# murdock_mcu_v1.net
KiCad netlist of a schematic drawn in EAGLE
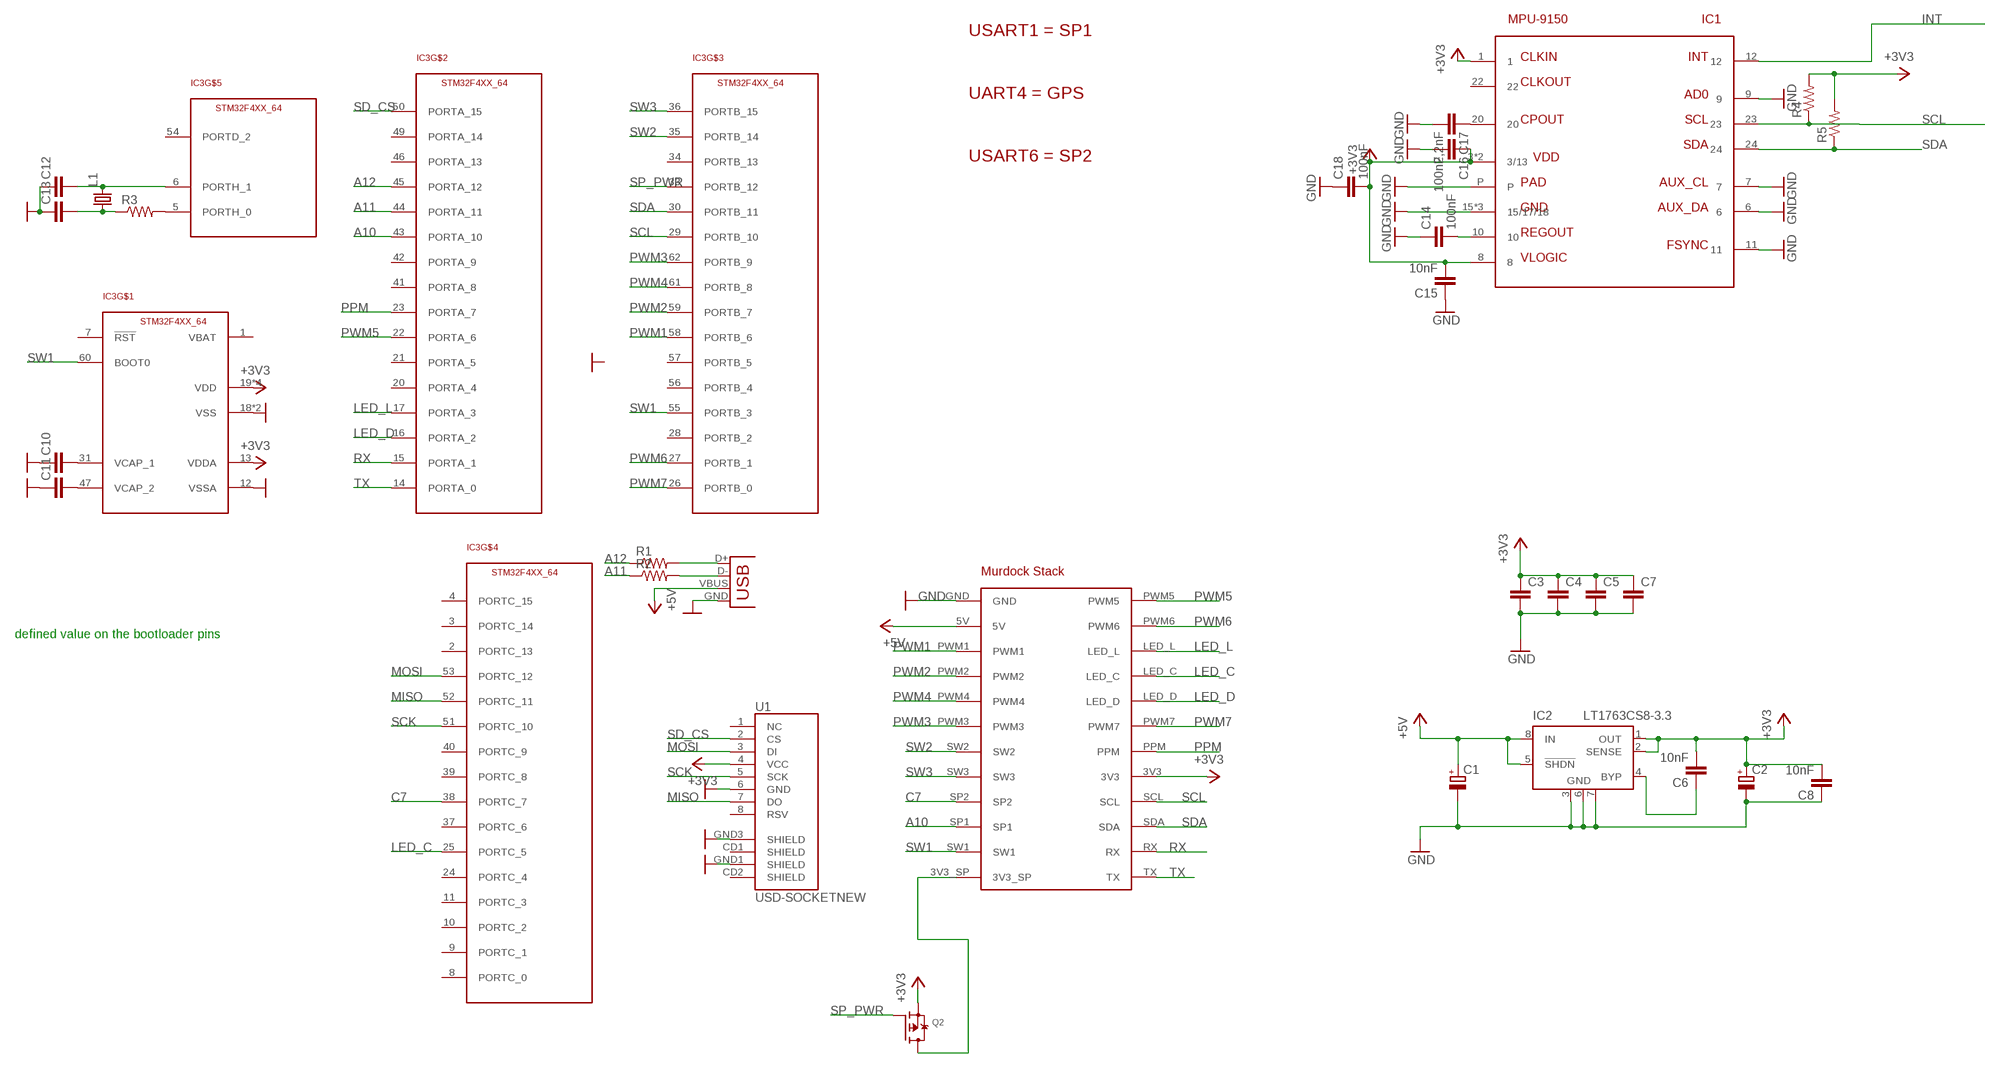
[diagram p0: schematic, sheet 1]

(export (version "E")
  (design (tool "Eeschema 10.0.6"))
  (components
    (comp (ref "C1")
      (value "CPOL-EUSMCD")
      (footprint "eagle-import:SMC_D")
      (libsource (lib "eagle-import") (part "CPOL-EUSMCD"))
    )
    (comp (ref "C2")
      (value "CPOL-EUSMCD")
      (footprint "eagle-import:SMC_D")
      (libsource (lib "eagle-import") (part "CPOL-EUSMCD"))
    )
    (comp (ref "C3")
      (value "CAP0402-CAP")
      (footprint "eagle-import:0402-CAP")
      (libsource (lib "eagle-import") (part "SparkFun-Capacitors_CAP0402-CAP"))
    )
    (comp (ref "C4")
      (value "CAP0402-CAP")
      (footprint "eagle-import:0402-CAP")
      (libsource (lib "eagle-import") (part "SparkFun-Capacitors_CAP0402-CAP"))
    )
    (comp (ref "C5")
      (value "CAP0402-CAP")
      (footprint "eagle-import:0402-CAP")
      (libsource (lib "eagle-import") (part "SparkFun-Capacitors_CAP0402-CAP"))
    )
    (comp (ref "C6")
      (value "10nF")
      (footprint "eagle-import:C0402")
      (libsource (lib "eagle-import") (part "C-EUC0402"))
    )
    (comp (ref "C7")
      (value "CAP0402-CAP")
      (footprint "eagle-import:0402-CAP")
      (libsource (lib "eagle-import") (part "SparkFun-Capacitors_CAP0402-CAP"))
    )
    (comp (ref "C8")
      (value "10nF")
      (footprint "eagle-import:C0402")
      (libsource (lib "eagle-import") (part "C-EUC0402"))
    )
    (comp (ref "C10")
      (value "CAP0805")
      (footprint "eagle-import:0805")
      (libsource (lib "eagle-import") (part "SparkFun-Capacitors_CAP0805"))
    )
    (comp (ref "C11")
      (value "CAP0805")
      (footprint "eagle-import:0805")
      (libsource (lib "eagle-import") (part "SparkFun-Capacitors_CAP0805"))
    )
    (comp (ref "C12")
      (value "CAP0402-CAP")
      (footprint "eagle-import:0402-CAP")
      (libsource (lib "eagle-import") (part "SparkFun-Capacitors_CAP0402-CAP"))
    )
    (comp (ref "C13")
      (value "CAP0402-CAP")
      (footprint "eagle-import:0402-CAP")
      (libsource (lib "eagle-import") (part "SparkFun-Capacitors_CAP0402-CAP"))
    )
    (comp (ref "C14")
      (value "100nF")
      (footprint "eagle-import:0402-CAP")
      (libsource (lib "eagle-import") (part "CAP0402-CAP"))
    )
    (comp (ref "C15")
      (value "10nF")
      (footprint "eagle-import:0402-CAP")
      (libsource (lib "eagle-import") (part "CAP0402-CAP"))
    )
    (comp (ref "C16")
      (value "100nF")
      (footprint "eagle-import:0402-CAP")
      (libsource (lib "eagle-import") (part "CAP0402-CAP"))
    )
    (comp (ref "C17")
      (value "2,2nF")
      (footprint "eagle-import:0402-CAP")
      (libsource (lib "eagle-import") (part "CAP0402-CAP"))
    )
    (comp (ref "C18")
      (value "100nF")
      (footprint "eagle-import:0402-CAP")
      (libsource (lib "eagle-import") (part "CAP0402-CAP"))
    )
    (comp (ref "IC1")
      (value "MPU-9150")
      (footprint "eagle-import:QFN24")
      (libsource (lib "eagle-import") (part "MPU-9150"))
    )
    (comp (ref "IC2")
      (value "LT1763CS8-3.3")
      (footprint "eagle-import:SOIC8")
      (libsource (lib "eagle-import") (part "LT1763CS8-3.3"))
    )
    (comp (ref "IC3")
      (value "STM32F4XX_64")
      (footprint "eagle-import:TQFP64")
      (libsource (lib "eagle-import") (part "STM32F4XX_64"))
    )
    (comp (ref "L1")
      (value "X22-OSCILLATOR")
      (footprint "eagle-import:X22")
      (libsource (lib "eagle-import") (part "X22-OSCILLATOR"))
    )
    (comp (ref "Q2")
      (value "MOSFET-P")
      (footprint "eagle-import:SOT23-R")
      (libsource (lib "eagle-import") (part "MOSFET-P"))
    )
    (comp (ref "R1")
      (value "RESISTOR0402-RES")
      (footprint "eagle-import:0402-RES")
      (libsource (lib "eagle-import") (part "SparkFun-Resistors_RESISTOR0402-RES"))
    )
    (comp (ref "R2")
      (value "RESISTOR0402-RES")
      (footprint "eagle-import:0402-RES")
      (libsource (lib "eagle-import") (part "SparkFun-Resistors_RESISTOR0402-RES"))
    )
    (comp (ref "R3")
      (value "RESISTOR0402-RES")
      (footprint "eagle-import:0402-RES")
      (libsource (lib "eagle-import") (part "SparkFun-Resistors_RESISTOR0402-RES"))
    )
    (comp (ref "R4")
      (value "RESISTOR0402-RES")
      (footprint "eagle-import:0402-RES")
      (libsource (lib "eagle-import") (part "RESISTOR0402-RES"))
    )
    (comp (ref "R5")
      (value "RESISTOR0402-RES")
      (footprint "eagle-import:0402-RES")
      (libsource (lib "eagle-import") (part "RESISTOR0402-RES"))
    )
    (comp (ref "U1")
      (value "USD-SOCKETNEW")
      (footprint "eagle-import:MICRO-SD-SOCKET-PP")
      (libsource (lib "eagle-import") (part "USD-SOCKETNEW"))
    )
    (comp (ref "X1")
      (value "USBSMD")
      (footprint "eagle-import:USB-MINIB")
      (libsource (lib "eagle-import") (part "USBSMD"))
    )
    (comp (ref "X2")
      (value "MURDOCK_STACK")
      (footprint "eagle-import:MURDOCK_STACK")
      (libsource (lib "eagle-import") (part "MURDOCK_STACK"))
    )
  )
  (nets
    (net (code "1") (name "+3V3") (class "Default")
      (node (ref "C15") (pin "2") (pinfunction "2_2") (pintype "passive"))
      (node (ref "C16") (pin "1") (pinfunction "1_1") (pintype "passive"))
      (node (ref "C18") (pin "2") (pinfunction "2_2") (pintype "passive"))
      (node (ref "C2") (pin "+") (pinfunction "+_+") (pintype "passive"))
      (node (ref "C3") (pin "1") (pinfunction "1_1") (pintype "passive"))
      (node (ref "C4") (pin "1") (pinfunction "1_1") (pintype "passive"))
      (node (ref "C5") (pin "1") (pinfunction "1_1") (pintype "passive"))
      (node (ref "C6") (pin "2") (pinfunction "2_2") (pintype "passive"))
      (node (ref "C7") (pin "1") (pinfunction "1_1") (pintype "passive"))
      (node (ref "C8") (pin "2") (pinfunction "2_2") (pintype "passive"))
      (node (ref "IC1") (pin "1") (pinfunction "1_1") (pintype "bidirectional"))
      (node (ref "IC1") (pin "13") (pinfunction "3/13_13") (pintype "bidirectional"))
      (node (ref "IC1") (pin "3") (pinfunction "3/13_3") (pintype "bidirectional"))
      (node (ref "IC1") (pin "8") (pinfunction "8_8") (pintype "bidirectional"))
      (node (ref "IC2") (pin "1") (pinfunction "OUT_1") (pintype "passive"))
      (node (ref "IC2") (pin "2") (pinfunction "SENSE_2") (pintype "input"))
      (node (ref "IC3") (pin "13") (pinfunction "VDDA_13") (pintype "bidirectional"))
      (node (ref "IC3") (pin "19") (pinfunction "VDD_19") (pintype "bidirectional"))
      (node (ref "IC3") (pin "32") (pinfunction "VDD_32") (pintype "bidirectional"))
      (node (ref "IC3") (pin "48") (pinfunction "VDD_48") (pintype "bidirectional"))
      (node (ref "IC3") (pin "64") (pinfunction "VDD_64") (pintype "bidirectional"))
      (node (ref "Q2") (pin "2") (pinfunction "S_2") (pintype "passive"))
      (node (ref "R4") (pin "2") (pinfunction "2_2") (pintype "passive"))
      (node (ref "R5") (pin "2") (pinfunction "2_2") (pintype "passive"))
      (node (ref "U1") (pin "4") (pinfunction "VCC_4") (pintype "bidirectional"))
      (node (ref "X2") (pin "3V3") (pinfunction "3V3_3V3") (pintype "bidirectional"))
    )
    (net (code "2") (name "+5V") (class "Default")
      (node (ref "C1") (pin "+") (pinfunction "+_+") (pintype "passive"))
      (node (ref "IC2") (pin "5") (pinfunction "~{SHDN}_5") (pintype "input"))
      (node (ref "IC2") (pin "8") (pinfunction "IN_8") (pintype "input"))
      (node (ref "X1") (pin "VBUS") (pinfunction "VBUS_VBUS") (pintype "bidirectional"))
      (node (ref "X2") (pin "5V") (pinfunction "5V_5V") (pintype "bidirectional"))
    )
    (net (code "3") (name "A10") (class "Default")
      (node (ref "IC3") (pin "43") (pinfunction "PORTA_10_43") (pintype "bidirectional"))
      (node (ref "X2") (pin "SP1") (pinfunction "SP1_SP1") (pintype "bidirectional"))
    )
    (net (code "4") (name "A11") (class "Default")
      (node (ref "IC3") (pin "44") (pinfunction "PORTA_11_44") (pintype "bidirectional"))
      (node (ref "R2") (pin "1") (pinfunction "1_1") (pintype "passive"))
    )
    (net (code "5") (name "A12") (class "Default")
      (node (ref "IC3") (pin "45") (pinfunction "PORTA_12_45") (pintype "bidirectional"))
      (node (ref "R1") (pin "1") (pinfunction "1_1") (pintype "passive"))
    )
    (net (code "6") (name "C7") (class "Default")
      (node (ref "IC3") (pin "38") (pinfunction "PORTC_7_38") (pintype "bidirectional"))
      (node (ref "X2") (pin "SP2") (pinfunction "SP2_SP2") (pintype "bidirectional"))
    )
    (net (code "7") (name "GND") (class "Default")
      (node (ref "C1") (pin "-") (pinfunction "-_-") (pintype "passive"))
      (node (ref "C10") (pin "1") (pinfunction "1_1") (pintype "passive"))
      (node (ref "C11") (pin "1") (pinfunction "1_1") (pintype "passive"))
      (node (ref "C12") (pin "1") (pinfunction "1_1") (pintype "passive"))
      (node (ref "C13") (pin "1") (pinfunction "1_1") (pintype "passive"))
      (node (ref "C14") (pin "1") (pinfunction "1_1") (pintype "passive"))
      (node (ref "C15") (pin "1") (pinfunction "1_1") (pintype "passive"))
      (node (ref "C16") (pin "2") (pinfunction "2_2") (pintype "passive"))
      (node (ref "C17") (pin "2") (pinfunction "2_2") (pintype "passive"))
      (node (ref "C18") (pin "1") (pinfunction "1_1") (pintype "passive"))
      (node (ref "C2") (pin "-") (pinfunction "-_-") (pintype "passive"))
      (node (ref "C3") (pin "2") (pinfunction "2_2") (pintype "passive"))
      (node (ref "C4") (pin "2") (pinfunction "2_2") (pintype "passive"))
      (node (ref "C5") (pin "2") (pinfunction "2_2") (pintype "passive"))
      (node (ref "C7") (pin "2") (pinfunction "2_2") (pintype "passive"))
      (node (ref "C8") (pin "1") (pinfunction "1_1") (pintype "passive"))
      (node (ref "IC1") (pin "11") (pinfunction "11_11") (pintype "bidirectional"))
      (node (ref "IC1") (pin "15") (pinfunction "15/17/18_15") (pintype "bidirectional"))
      (node (ref "IC1") (pin "17") (pinfunction "15/17/18_17") (pintype "bidirectional"))
      (node (ref "IC1") (pin "18") (pinfunction "15/17/18_18") (pintype "bidirectional"))
      (node (ref "IC1") (pin "6") (pinfunction "6_6") (pintype "bidirectional"))
      (node (ref "IC1") (pin "7") (pinfunction "7_7") (pintype "bidirectional"))
      (node (ref "IC1") (pin "9") (pinfunction "9_9") (pintype "bidirectional"))
      (node (ref "IC1") (pin "P") (pinfunction "P_P") (pintype "bidirectional"))
      (node (ref "IC2") (pin "3") (pinfunction "GND_3") (pintype "power_in"))
      (node (ref "IC2") (pin "6") (pinfunction "GND_6") (pintype "power_in"))
      (node (ref "IC2") (pin "7") (pinfunction "GND_7") (pintype "power_in"))
      (node (ref "IC3") (pin "12") (pinfunction "VSSA_12") (pintype "bidirectional"))
      (node (ref "IC3") (pin "18") (pinfunction "VSS_18") (pintype "bidirectional"))
      (node (ref "IC3") (pin "63") (pinfunction "VSS_63") (pintype "bidirectional"))
      (node (ref "U1") (pin "6") (pinfunction "GND_6") (pintype "bidirectional"))
      (node (ref "U1") (pin "GND1") (pinfunction "SHIELD_GND1") (pintype "bidirectional"))
      (node (ref "U1") (pin "GND3") (pinfunction "SHIELD_GND3") (pintype "bidirectional"))
      (node (ref "X1") (pin "GND") (pinfunction "GND_GND") (pintype "bidirectional"))
      (node (ref "X2") (pin "GND") (pinfunction "GND_GND") (pintype "bidirectional"))
    )
    (net (code "8") (name "INT") (class "Default")
      (node (ref "IC1") (pin "12") (pinfunction "12_12") (pintype "bidirectional"))
    )
    (net (code "9") (name "LED_C") (class "Default")
      (node (ref "IC3") (pin "25") (pinfunction "PORTC_5_25") (pintype "bidirectional"))
      (node (ref "X2") (pin "LED_C") (pinfunction "LED_C_LED_C") (pintype "bidirectional"))
    )
    (net (code "10") (name "LED_D") (class "Default")
      (node (ref "IC3") (pin "16") (pinfunction "PORTA_2_16") (pintype "bidirectional"))
      (node (ref "X2") (pin "LED_D") (pinfunction "LED_D_LED_D") (pintype "bidirectional"))
    )
    (net (code "11") (name "LED_L") (class "Default")
      (node (ref "IC3") (pin "17") (pinfunction "PORTA_3_17") (pintype "bidirectional"))
      (node (ref "X2") (pin "LED_L") (pinfunction "LED_L_LED_L") (pintype "bidirectional"))
    )
    (net (code "12") (name "MISO") (class "Default")
      (node (ref "IC3") (pin "52") (pinfunction "PORTC_11_52") (pintype "bidirectional"))
      (node (ref "U1") (pin "7") (pinfunction "DO_7") (pintype "bidirectional"))
    )
    (net (code "13") (name "MOSI") (class "Default")
      (node (ref "IC3") (pin "53") (pinfunction "PORTC_12_53") (pintype "bidirectional"))
      (node (ref "U1") (pin "3") (pinfunction "DI_3") (pintype "bidirectional"))
    )
    (net (code "14") (name "Net-(C13-Pad2)") (class "Default")
      (node (ref "C13") (pin "2") (pinfunction "2_2") (pintype "passive"))
      (node (ref "L1") (pin "1") (pinfunction "1_1") (pintype "passive"))
      (node (ref "R3") (pin "1") (pinfunction "1_1") (pintype "passive"))
    )
    (net (code "15") (name "Net-(C14-Pad2)") (class "Default")
      (node (ref "C14") (pin "2") (pinfunction "2_2") (pintype "passive"))
      (node (ref "IC1") (pin "10") (pinfunction "10_10") (pintype "bidirectional"))
    )
    (net (code "16") (name "Net-(C17-Pad1)") (class "Default")
      (node (ref "C17") (pin "1") (pinfunction "1_1") (pintype "passive"))
      (node (ref "IC1") (pin "20") (pinfunction "20_20") (pintype "bidirectional"))
    )
    (net (code "17") (name "Net-(IC2-BYP)") (class "Default")
      (node (ref "C6") (pin "1") (pinfunction "1_1") (pintype "passive"))
      (node (ref "IC2") (pin "4") (pinfunction "BYP_4") (pintype "input"))
    )
    (net (code "18") (name "Net-(IC3A-VCAP_1)") (class "Default")
      (node (ref "C10") (pin "2") (pinfunction "2_2") (pintype "passive"))
      (node (ref "IC3") (pin "31") (pinfunction "VCAP_1_31") (pintype "bidirectional"))
    )
    (net (code "19") (name "Net-(IC3A-VCAP_2)") (class "Default")
      (node (ref "C11") (pin "2") (pinfunction "2_2") (pintype "passive"))
      (node (ref "IC3") (pin "47") (pinfunction "VCAP_2_47") (pintype "bidirectional"))
    )
    (net (code "20") (name "Net-(IC3E-PORTH_0)") (class "Default")
      (node (ref "IC3") (pin "5") (pinfunction "PORTH_0_5") (pintype "bidirectional"))
      (node (ref "R3") (pin "2") (pinfunction "2_2") (pintype "passive"))
    )
    (net (code "21") (name "Net-(IC3E-PORTH_1)") (class "Default")
      (node (ref "C12") (pin "2") (pinfunction "2_2") (pintype "passive"))
      (node (ref "IC3") (pin "6") (pinfunction "PORTH_1_6") (pintype "bidirectional"))
      (node (ref "L1") (pin "3") (pinfunction "2_3") (pintype "passive"))
    )
    (net (code "22") (name "Net-(Q2-D)") (class "Default")
      (node (ref "Q2") (pin "3") (pinfunction "D_3") (pintype "passive"))
      (node (ref "X2") (pin "3V3_SP") (pinfunction "3V3_SP_3V3_SP") (pintype "bidirectional"))
    )
    (net (code "23") (name "Net-(R1-Pad2)") (class "Default")
      (node (ref "R1") (pin "2") (pinfunction "2_2") (pintype "passive"))
      (node (ref "X1") (pin "D+") (pinfunction "D+_D+") (pintype "bidirectional"))
    )
    (net (code "24") (name "Net-(R2-Pad2)") (class "Default")
      (node (ref "R2") (pin "2") (pinfunction "2_2") (pintype "passive"))
      (node (ref "X1") (pin "D-") (pinfunction "D-_D-") (pintype "bidirectional"))
    )
    (net (code "25") (name "PPM") (class "Default")
      (node (ref "IC3") (pin "23") (pinfunction "PORTA_7_23") (pintype "bidirectional"))
      (node (ref "X2") (pin "PPM") (pinfunction "PPM_PPM") (pintype "bidirectional"))
    )
    (net (code "26") (name "PWM1") (class "Default")
      (node (ref "IC3") (pin "58") (pinfunction "PORTB_6_58") (pintype "bidirectional"))
      (node (ref "X2") (pin "PWM1") (pinfunction "PWM1_PWM1") (pintype "bidirectional"))
    )
    (net (code "27") (name "PWM2") (class "Default")
      (node (ref "IC3") (pin "59") (pinfunction "PORTB_7_59") (pintype "bidirectional"))
      (node (ref "X2") (pin "PWM2") (pinfunction "PWM2_PWM2") (pintype "bidirectional"))
    )
    (net (code "28") (name "PWM3") (class "Default")
      (node (ref "IC3") (pin "62") (pinfunction "PORTB_9_62") (pintype "bidirectional"))
      (node (ref "X2") (pin "PWM3") (pinfunction "PWM3_PWM3") (pintype "bidirectional"))
    )
    (net (code "29") (name "PWM4") (class "Default")
      (node (ref "IC3") (pin "61") (pinfunction "PORTB_8_61") (pintype "bidirectional"))
      (node (ref "X2") (pin "PWM4") (pinfunction "PWM4_PWM4") (pintype "bidirectional"))
    )
    (net (code "30") (name "PWM5") (class "Default")
      (node (ref "IC3") (pin "22") (pinfunction "PORTA_6_22") (pintype "bidirectional"))
      (node (ref "X2") (pin "PWM5") (pinfunction "PWM5_PWM5") (pintype "bidirectional"))
    )
    (net (code "31") (name "PWM6") (class "Default")
      (node (ref "IC3") (pin "27") (pinfunction "PORTB_1_27") (pintype "bidirectional"))
      (node (ref "X2") (pin "PWM6") (pinfunction "PWM6_PWM6") (pintype "bidirectional"))
    )
    (net (code "32") (name "PWM7") (class "Default")
      (node (ref "IC3") (pin "26") (pinfunction "PORTB_0_26") (pintype "bidirectional"))
      (node (ref "X2") (pin "PWM7") (pinfunction "PWM7_PWM7") (pintype "bidirectional"))
    )
    (net (code "33") (name "RX") (class "Default")
      (node (ref "IC3") (pin "15") (pinfunction "PORTA_1_15") (pintype "bidirectional"))
      (node (ref "X2") (pin "RX") (pinfunction "RX_RX") (pintype "bidirectional"))
    )
    (net (code "34") (name "SCK") (class "Default")
      (node (ref "IC3") (pin "51") (pinfunction "PORTC_10_51") (pintype "bidirectional"))
      (node (ref "U1") (pin "5") (pinfunction "SCK_5") (pintype "bidirectional"))
    )
    (net (code "35") (name "SCL") (class "Default")
      (node (ref "IC1") (pin "23") (pinfunction "23_23") (pintype "bidirectional"))
      (node (ref "IC3") (pin "29") (pinfunction "PORTB_10_29") (pintype "bidirectional"))
      (node (ref "R4") (pin "1") (pinfunction "1_1") (pintype "passive"))
      (node (ref "X2") (pin "SCL") (pinfunction "SCL_SCL") (pintype "bidirectional"))
    )
    (net (code "36") (name "SDA") (class "Default")
      (node (ref "IC1") (pin "24") (pinfunction "24_24") (pintype "bidirectional"))
      (node (ref "IC3") (pin "30") (pinfunction "PORTB_11_30") (pintype "bidirectional"))
      (node (ref "R5") (pin "1") (pinfunction "1_1") (pintype "passive"))
      (node (ref "X2") (pin "SDA") (pinfunction "SDA_SDA") (pintype "bidirectional"))
    )
    (net (code "37") (name "SD_CS") (class "Default")
      (node (ref "IC3") (pin "50") (pinfunction "PORTA_15_50") (pintype "bidirectional"))
      (node (ref "U1") (pin "2") (pinfunction "CS_2") (pintype "bidirectional"))
    )
    (net (code "38") (name "SP_PWR") (class "Default")
      (node (ref "IC3") (pin "33") (pinfunction "PORTB_12_33") (pintype "bidirectional"))
      (node (ref "Q2") (pin "1") (pinfunction "G_1") (pintype "passive"))
    )
    (net (code "39") (name "SW1") (class "Default")
      (node (ref "IC3") (pin "55") (pinfunction "PORTB_3_55") (pintype "bidirectional"))
      (node (ref "IC3") (pin "60") (pinfunction "BOOT0_60") (pintype "bidirectional"))
      (node (ref "X2") (pin "SW1") (pinfunction "SW1_SW1") (pintype "bidirectional"))
    )
    (net (code "40") (name "SW2") (class "Default")
      (node (ref "IC3") (pin "35") (pinfunction "PORTB_14_35") (pintype "bidirectional"))
      (node (ref "X2") (pin "SW2") (pinfunction "SW2_SW2") (pintype "bidirectional"))
    )
    (net (code "41") (name "SW3") (class "Default")
      (node (ref "IC3") (pin "36") (pinfunction "PORTB_15_36") (pintype "bidirectional"))
      (node (ref "X2") (pin "SW3") (pinfunction "SW3_SW3") (pintype "bidirectional"))
    )
    (net (code "42") (name "TX") (class "Default")
      (node (ref "IC3") (pin "14") (pinfunction "PORTA_0_14") (pintype "bidirectional"))
      (node (ref "X2") (pin "TX") (pinfunction "TX_TX") (pintype "bidirectional"))
    )
    (net (code "43") (name "unconnected-(IC1-Pad22)") (class "Default")
      (node (ref "IC1") (pin "22") (pinfunction "22_22") (pintype "bidirectional"))
    )
    (net (code "44") (name "unconnected-(IC3A-VBAT-Pad1)") (class "Default")
      (node (ref "IC3") (pin "1") (pinfunction "VBAT_1") (pintype "bidirectional"))
    )
    (net (code "45") (name "unconnected-(IC3A-~{RST}-Pad7)") (class "Default")
      (node (ref "IC3") (pin "7") (pinfunction "~{RST}_7") (pintype "bidirectional"))
    )
    (net (code "46") (name "unconnected-(IC3B-PORTA_4-Pad20)") (class "Default")
      (node (ref "IC3") (pin "20") (pinfunction "PORTA_4_20") (pintype "bidirectional"))
    )
    (net (code "47") (name "unconnected-(IC3B-PORTA_5-Pad21)") (class "Default")
      (node (ref "IC3") (pin "21") (pinfunction "PORTA_5_21") (pintype "bidirectional"))
    )
    (net (code "48") (name "unconnected-(IC3B-PORTA_8-Pad41)") (class "Default")
      (node (ref "IC3") (pin "41") (pinfunction "PORTA_8_41") (pintype "bidirectional"))
    )
    (net (code "49") (name "unconnected-(IC3B-PORTA_9-Pad42)") (class "Default")
      (node (ref "IC3") (pin "42") (pinfunction "PORTA_9_42") (pintype "bidirectional"))
    )
    (net (code "50") (name "unconnected-(IC3B-PORTA_13-Pad46)") (class "Default")
      (node (ref "IC3") (pin "46") (pinfunction "PORTA_13_46") (pintype "bidirectional"))
    )
    (net (code "51") (name "unconnected-(IC3B-PORTA_14-Pad49)") (class "Default")
      (node (ref "IC3") (pin "49") (pinfunction "PORTA_14_49") (pintype "bidirectional"))
    )
    (net (code "52") (name "unconnected-(IC3C-PORTB_2-Pad28)") (class "Default")
      (node (ref "IC3") (pin "28") (pinfunction "PORTB_2_28") (pintype "bidirectional"))
    )
    (net (code "53") (name "unconnected-(IC3C-PORTB_4-Pad56)") (class "Default")
      (node (ref "IC3") (pin "56") (pinfunction "PORTB_4_56") (pintype "bidirectional"))
    )
    (net (code "54") (name "unconnected-(IC3C-PORTB_5-Pad57)") (class "Default")
      (node (ref "IC3") (pin "57") (pinfunction "PORTB_5_57") (pintype "bidirectional"))
    )
    (net (code "55") (name "unconnected-(IC3C-PORTB_13-Pad34)") (class "Default")
      (node (ref "IC3") (pin "34") (pinfunction "PORTB_13_34") (pintype "bidirectional"))
    )
    (net (code "56") (name "unconnected-(IC3D-PORTC_0-Pad8)") (class "Default")
      (node (ref "IC3") (pin "8") (pinfunction "PORTC_0_8") (pintype "bidirectional"))
    )
    (net (code "57") (name "unconnected-(IC3D-PORTC_1-Pad9)") (class "Default")
      (node (ref "IC3") (pin "9") (pinfunction "PORTC_1_9") (pintype "bidirectional"))
    )
    (net (code "58") (name "unconnected-(IC3D-PORTC_2-Pad10)") (class "Default")
      (node (ref "IC3") (pin "10") (pinfunction "PORTC_2_10") (pintype "bidirectional"))
    )
    (net (code "59") (name "unconnected-(IC3D-PORTC_3-Pad11)") (class "Default")
      (node (ref "IC3") (pin "11") (pinfunction "PORTC_3_11") (pintype "bidirectional"))
    )
    (net (code "60") (name "unconnected-(IC3D-PORTC_4-Pad24)") (class "Default")
      (node (ref "IC3") (pin "24") (pinfunction "PORTC_4_24") (pintype "bidirectional"))
    )
    (net (code "61") (name "unconnected-(IC3D-PORTC_6-Pad37)") (class "Default")
      (node (ref "IC3") (pin "37") (pinfunction "PORTC_6_37") (pintype "bidirectional"))
    )
    (net (code "62") (name "unconnected-(IC3D-PORTC_8-Pad39)") (class "Default")
      (node (ref "IC3") (pin "39") (pinfunction "PORTC_8_39") (pintype "bidirectional"))
    )
    (net (code "63") (name "unconnected-(IC3D-PORTC_9-Pad40)") (class "Default")
      (node (ref "IC3") (pin "40") (pinfunction "PORTC_9_40") (pintype "bidirectional"))
    )
    (net (code "64") (name "unconnected-(IC3D-PORTC_13-Pad2)") (class "Default")
      (node (ref "IC3") (pin "2") (pinfunction "PORTC_13_2") (pintype "bidirectional"))
    )
    (net (code "65") (name "unconnected-(IC3D-PORTC_14-Pad3)") (class "Default")
      (node (ref "IC3") (pin "3") (pinfunction "PORTC_14_3") (pintype "bidirectional"))
    )
    (net (code "66") (name "unconnected-(IC3D-PORTC_15-Pad4)") (class "Default")
      (node (ref "IC3") (pin "4") (pinfunction "PORTC_15_4") (pintype "bidirectional"))
    )
    (net (code "67") (name "unconnected-(IC3E-PORTD_2-Pad54)") (class "Default")
      (node (ref "IC3") (pin "54") (pinfunction "PORTD_2_54") (pintype "bidirectional"))
    )
    (net (code "68") (name "unconnected-(U1-NC-Pad1)") (class "Default")
      (node (ref "U1") (pin "1") (pinfunction "NC_1") (pintype "bidirectional"))
    )
    (net (code "69") (name "unconnected-(U1-RSV-Pad8)") (class "Default")
      (node (ref "U1") (pin "8") (pinfunction "RSV_8") (pintype "bidirectional"))
    )
    (net (code "70") (name "unconnected-(U1-SHIELD-PadCD1)") (class "Default")
      (node (ref "U1") (pin "CD1") (pinfunction "SHIELD_CD1") (pintype "bidirectional"))
    )
    (net (code "71") (name "unconnected-(U1-SHIELD-PadCD2)") (class "Default")
      (node (ref "U1") (pin "CD2") (pinfunction "SHIELD_CD2") (pintype "bidirectional"))
    )
  )
)
